# Analogue_Output.net
KiCad netlist of a schematic drawn in Altium Designer
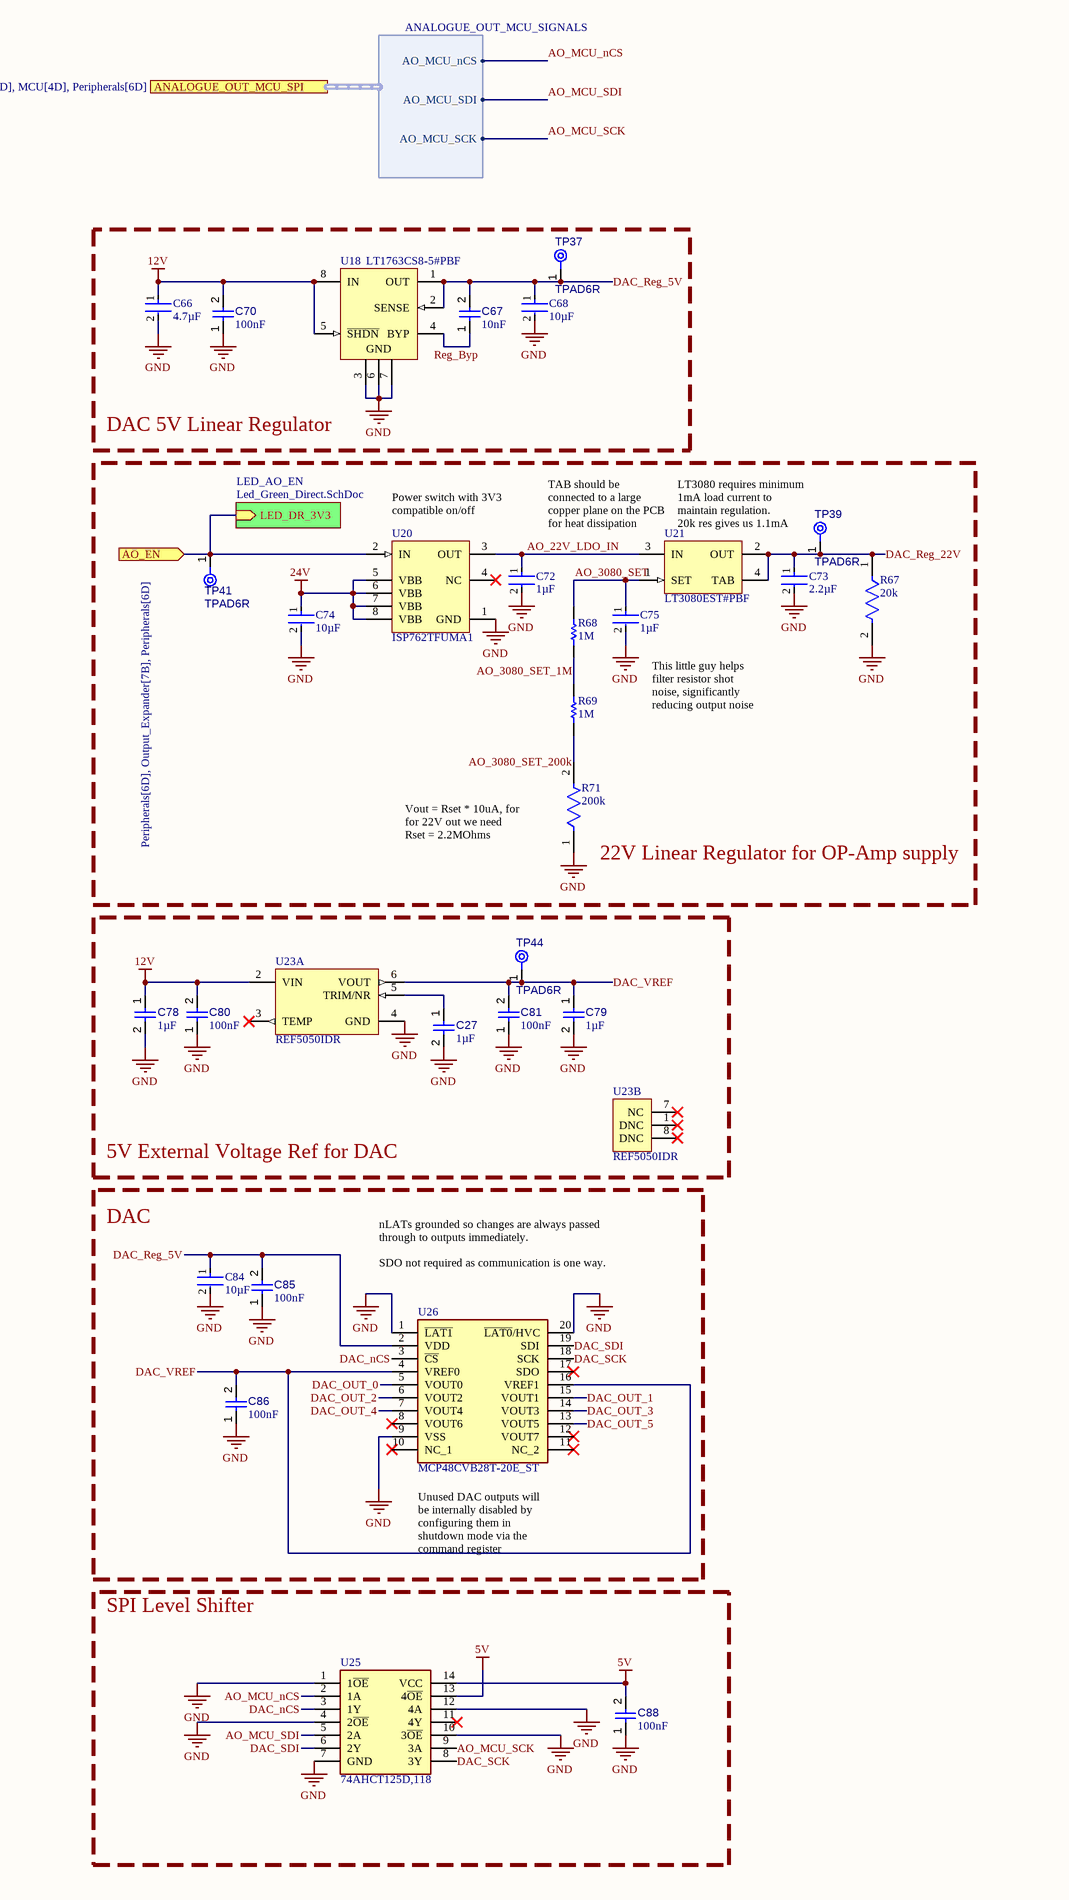
[diagram p0:  Analogue_Output.SchDoc, left]
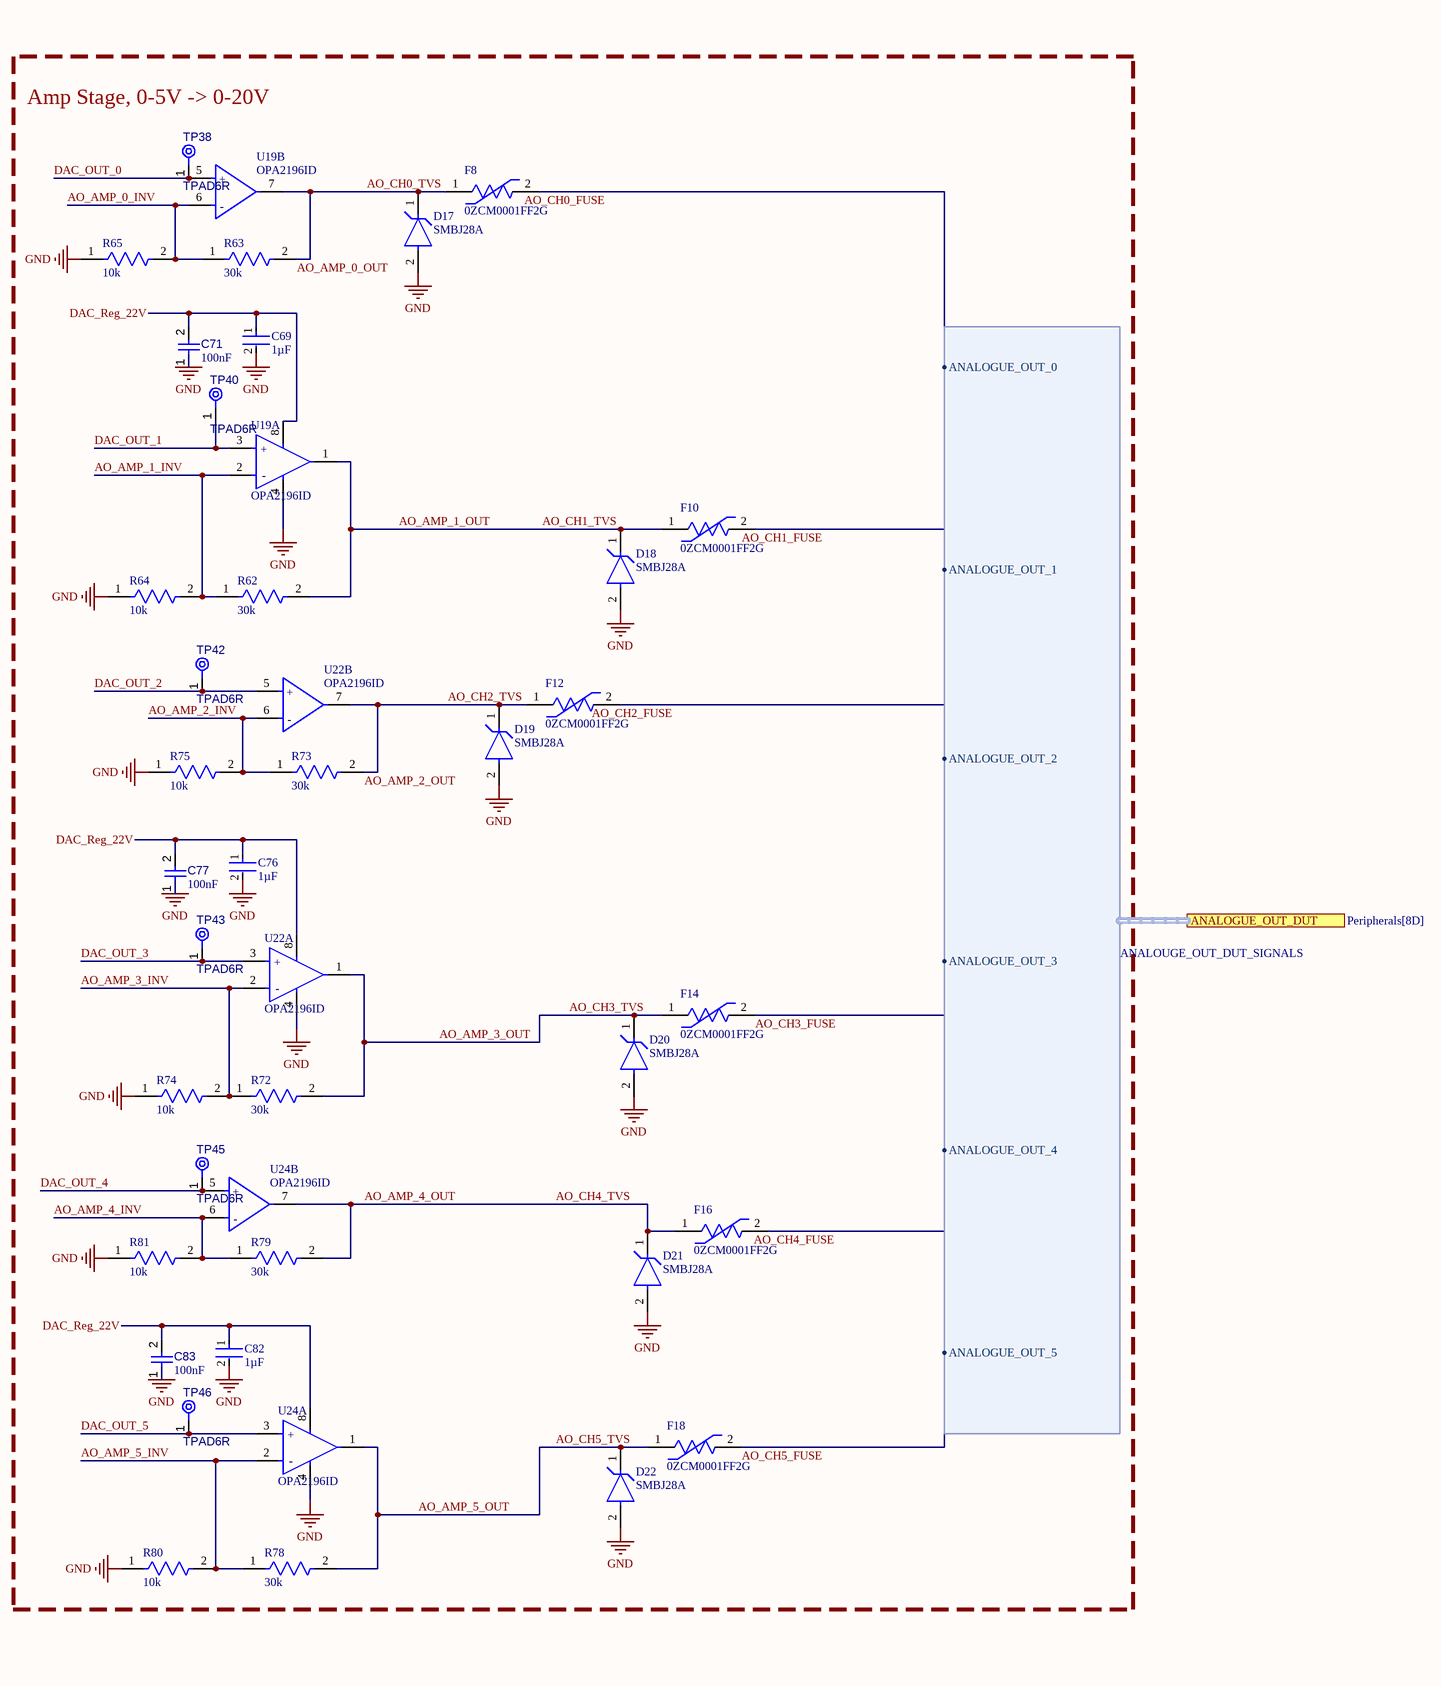
[diagram p1:  Analogue_Output.SchDoc, right]

(export (version "E")
  (design (tool "Eeschema 10.0.6"))
  (components
    (comp (ref "C27")
      (value "1µF")
      (footprint "CAPC1608X90X40LL10T20")
      (description "Chip Capacitor, 1 uF, +/- 10%, 25 V, 0603 (1608 Metric)")
      (fields (field (name "TOLERANCE") "10%") (field (name "Comment") "Capacitor 1 uF +/- 10% 25 V 0603"))
      (libsource (lib "HIL RIG FYP") (part "CAP-NP-2"))
    )
    (comp (ref "C66")
      (value "4.7µF")
      (footprint "FP-GRM21B-0_2-e0_2_0_7-MFG")
      (description "50V 4.7uF X7R ±10% 0805 Multilayer Ceramic Capacitors MLCC - SMD/SMT ROHS")
      (fields (field (name "TOLERANCE") "10%") (field (name "Comment") "GRM21BZ71H475KE15L"))
      (libsource (lib "HIL RIG FYP") (part "b4654b650e69147ec39a6b967a45e02"))
    )
    (comp (ref "C67")
      (value "10nF")
      (footprint "CAPC0402(1005)60_L")
      (description "Chip Capacitor, 10nF +/-20%, 50V, 0402, Thickness 0.6 mm")
      (fields (field (name "TOLERANCE") "5%") (field (name "Comment") "Capacitor 10nF +/-20% 50V 0402"))
      (libsource (lib "HIL RIG FYP") (part "CAP-NP-2"))
    )
    (comp (ref "C68")
      (value "10µF")
      (footprint "FP-GRM31C-0_2-e0_3_0_8-IPC_C")
      (description "25V 10uF X7R ±10% 1206 Multilayer Ceramic Capacitors MLCC - SMD/SMT ROHS")
      (fields (field (name "TOLERANCE") "10%") (field (name "VOLTAGE") "25V"))
      (libsource (lib "HIL RIG FYP") (part "02cd4be3c70576c341d710602a673aa"))
    )
    (comp (ref "C69")
      (value "1µF")
      (footprint "FP-CC0603-DB-IPC_B")
      (description "50V 1uF X7R ±10% 0603 Multilayer Ceramic Capacitors MLCC - SMD/SMT ROHS")
      (fields (field (name "TOLERANCE") "10%") (field (name "Comment") "CC0603KRX7R9BB105"))
      (libsource (lib "HIL RIG FYP") (part "11868f565c42a9108669ba33697ecf6"))
    )
    (comp (ref "C70")
      (value "100nF")
      (footprint "CAPC1608X90X40NL10T20")
      (description "Chip Capacitor, 100 nF, +/- 10%, 50 V, 0603 (1608 Metric)")
      (fields (field (name "TOLERANCE") "10%") (field (name "Comment") "Capacitor 100 nF +/-10% 50 V 0603"))
      (libsource (lib "HIL RIG FYP") (part "CAP-NP-2"))
    )
    (comp (ref "C71")
      (value "100nF")
      (footprint "CAPC1608X90X40NL10T20")
      (description "Chip Capacitor, 100 nF, +/- 10%, 50 V, 0603 (1608 Metric)")
      (fields (field (name "TOLERANCE") "10%") (field (name "Comment") "Capacitor 100 nF +/-10% 50 V 0603"))
      (libsource (lib "HIL RIG FYP") (part "CAP-NP-2"))
    )
    (comp (ref "C72")
      (value "1µF")
      (footprint "FP-CC0603-DB-IPC_B")
      (description "50V 1uF X7R ±10% 0603 Multilayer Ceramic Capacitors MLCC - SMD/SMT ROHS")
      (fields (field (name "TOLERANCE") "10%") (field (name "Comment") "CC0603KRX7R9BB105"))
      (libsource (lib "HIL RIG FYP") (part "11868f565c42a9108669ba33697ecf6"))
    )
    (comp (ref "C73")
      (value "2.2µF")
      (footprint "FP-CC0805-0_85-IPC_A")
      (description "50V 2.2uF X5R ±10% 0805 Multilayer Ceramic Capacitors MLCC - SMD/SMT ROHS")
      (fields (field (name "TOLERANCE") "10%") (field (name "Comment") "CC0805KKX5R9BB225"))
      (libsource (lib "HIL RIG FYP") (part "11868f565c42a9108669ba33697ecf6"))
    )
    (comp (ref "C74")
      (value "10µF")
      (footprint "FP-GRM188-0_2-IPC_C")
      (description "35V 10uF X5R ±20% 0603 Multilayer Ceramic Capacitors MLCC - SMD/SMT ROHS")
      (fields (field (name "TOLERANCE") "20%") (field (name "Comment") "GRM188R6YA106MA73D"))
      (libsource (lib "HIL RIG FYP") (part "11868f565c42a9108669ba33697ecf6"))
    )
    (comp (ref "C75")
      (value "1µF")
      (footprint "FP-CC0603-DB-IPC_B")
      (description "50V 1uF X7R ±10% 0603 Multilayer Ceramic Capacitors MLCC - SMD/SMT ROHS")
      (fields (field (name "TOLERANCE") "10%") (field (name "Comment") "CC0603KRX7R9BB105"))
      (libsource (lib "HIL RIG FYP") (part "11868f565c42a9108669ba33697ecf6"))
    )
    (comp (ref "C76")
      (value "1µF")
      (footprint "FP-CC0603-DB-IPC_B")
      (description "50V 1uF X7R ±10% 0603 Multilayer Ceramic Capacitors MLCC - SMD/SMT ROHS")
      (fields (field (name "TOLERANCE") "10%") (field (name "Comment") "CC0603KRX7R9BB105"))
      (libsource (lib "HIL RIG FYP") (part "11868f565c42a9108669ba33697ecf6"))
    )
    (comp (ref "C77")
      (value "100nF")
      (footprint "CAPC1608X90X40NL10T20")
      (description "Chip Capacitor, 100 nF, +/- 10%, 50 V, 0603 (1608 Metric)")
      (fields (field (name "TOLERANCE") "10%") (field (name "Comment") "Capacitor 100 nF +/-10% 50 V 0603"))
      (libsource (lib "HIL RIG FYP") (part "CAP-NP-2"))
    )
    (comp (ref "C78")
      (value "1µF")
      (footprint "CAPC1608X90X40LL10T20")
      (description "Chip Capacitor, 1 uF, +/- 10%, 25 V, 0603 (1608 Metric)")
      (fields (field (name "TOLERANCE") "10%") (field (name "Comment") "Capacitor 1 uF +/- 10% 25 V 0603"))
      (libsource (lib "HIL RIG FYP") (part "CAP-NP-2"))
    )
    (comp (ref "C79")
      (value "1µF")
      (footprint "CAPC1608X90X40LL10T20")
      (description "Chip Capacitor, 1 uF, +/- 10%, 25 V, 0603 (1608 Metric)")
      (fields (field (name "TOLERANCE") "10%") (field (name "Comment") "Capacitor 1 uF +/- 10% 25 V 0603"))
      (libsource (lib "HIL RIG FYP") (part "CAP-NP-2"))
    )
    (comp (ref "C80")
      (value "100nF")
      (footprint "CAPC1608X90X40NL10T20")
      (description "Chip Capacitor, 100 nF, +/- 10%, 50 V, 0603 (1608 Metric)")
      (fields (field (name "TOLERANCE") "10%") (field (name "Comment") "Capacitor 100 nF +/-10% 50 V 0603"))
      (libsource (lib "HIL RIG FYP") (part "CAP-NP-2"))
    )
    (comp (ref "C81")
      (value "100nF")
      (footprint "CAPC1608X90X40NL10T20")
      (description "Chip Capacitor, 100 nF, +/- 10%, 50 V, 0603 (1608 Metric)")
      (fields (field (name "TOLERANCE") "10%") (field (name "Comment") "Capacitor 100 nF +/-10% 50 V 0603"))
      (libsource (lib "HIL RIG FYP") (part "CAP-NP-2"))
    )
    (comp (ref "C82")
      (value "1µF")
      (footprint "FP-CC0603-DB-IPC_B")
      (description "50V 1uF X7R ±10% 0603 Multilayer Ceramic Capacitors MLCC - SMD/SMT ROHS")
      (fields (field (name "TOLERANCE") "10%") (field (name "Comment") "CC0603KRX7R9BB105"))
      (libsource (lib "HIL RIG FYP") (part "11868f565c42a9108669ba33697ecf6"))
    )
    (comp (ref "C83")
      (value "100nF")
      (footprint "CAPC1608X90X40NL10T20")
      (description "Chip Capacitor, 100 nF, +/- 10%, 50 V, 0603 (1608 Metric)")
      (fields (field (name "TOLERANCE") "10%") (field (name "Comment") "Capacitor 100 nF +/-10% 50 V 0603"))
      (libsource (lib "HIL RIG FYP") (part "CAP-NP-2"))
    )
    (comp (ref "C84")
      (value "10µF")
      (footprint "FP-GRM31C-0_2-e0_3_0_8-IPC_C")
      (description "25V 10uF X7R ±10% 1206 Multilayer Ceramic Capacitors MLCC - SMD/SMT ROHS")
      (fields (field (name "TOLERANCE") "10%") (field (name "VOLTAGE") "25V"))
      (libsource (lib "HIL RIG FYP") (part "02cd4be3c70576c341d710602a673aa"))
    )
    (comp (ref "C85")
      (value "100nF")
      (footprint "CAPC1608X90X40NL10T20")
      (description "Chip Capacitor, 100 nF, +/- 10%, 50 V, 0603 (1608 Metric)")
      (fields (field (name "TOLERANCE") "10%") (field (name "Comment") "Capacitor 100 nF +/-10% 50 V 0603"))
      (libsource (lib "HIL RIG FYP") (part "CAP-NP-2"))
    )
    (comp (ref "C86")
      (value "100nF")
      (footprint "CAPC1608X90X40NL10T20")
      (description "Chip Capacitor, 100 nF, +/- 10%, 50 V, 0603 (1608 Metric)")
      (fields (field (name "TOLERANCE") "10%") (field (name "Comment") "Capacitor 100 nF +/-10% 50 V 0603"))
      (libsource (lib "HIL RIG FYP") (part "CAP-NP-2"))
    )
    (comp (ref "C88")
      (value "100nF")
      (footprint "CAPC1608X90X40NL10T20")
      (description "Chip Capacitor, 100 nF, +/- 10%, 50 V, 0603 (1608 Metric)")
      (fields (field (name "TOLERANCE") "10%") (field (name "Comment") "Capacitor 100 nF +/-10% 50 V 0603"))
      (libsource (lib "HIL RIG FYP") (part "CAP-NP-2"))
    )
    (comp (ref "D17")
      (value "SMBJ28A")
      (footprint "FP-SMBJ-MFG")
      (description "Tvs Diodes & Esd Suppressors; SMBJ28A; Littelfuse; 28 V; 45.4 V; 31.1 V; 31.1 V")
      (fields (field (name "VOLTAGE") "28V"))
      (libsource (lib "HIL RIG FYP") (part "f813f71cba58e380607f5dd3caf9714"))
    )
    (comp (ref "D18")
      (value "SMBJ28A")
      (footprint "FP-SMBJ-MFG")
      (description "Tvs Diodes & Esd Suppressors; SMBJ28A; Littelfuse; 28 V; 45.4 V; 31.1 V; 31.1 V")
      (fields (field (name "VOLTAGE") "28V"))
      (libsource (lib "HIL RIG FYP") (part "f813f71cba58e380607f5dd3caf9714"))
    )
    (comp (ref "D19")
      (value "SMBJ28A")
      (footprint "FP-SMBJ-MFG")
      (description "Tvs Diodes & Esd Suppressors; SMBJ28A; Littelfuse; 28 V; 45.4 V; 31.1 V; 31.1 V")
      (fields (field (name "VOLTAGE") "28V"))
      (libsource (lib "HIL RIG FYP") (part "f813f71cba58e380607f5dd3caf9714"))
    )
    (comp (ref "D20")
      (value "SMBJ28A")
      (footprint "FP-SMBJ-MFG")
      (description "Tvs Diodes & Esd Suppressors; SMBJ28A; Littelfuse; 28 V; 45.4 V; 31.1 V; 31.1 V")
      (fields (field (name "VOLTAGE") "28V"))
      (libsource (lib "HIL RIG FYP") (part "f813f71cba58e380607f5dd3caf9714"))
    )
    (comp (ref "D21")
      (value "SMBJ28A")
      (footprint "FP-SMBJ-MFG")
      (description "Tvs Diodes & Esd Suppressors; SMBJ28A; Littelfuse; 28 V; 45.4 V; 31.1 V; 31.1 V")
      (fields (field (name "VOLTAGE") "28V"))
      (libsource (lib "HIL RIG FYP") (part "f813f71cba58e380607f5dd3caf9714"))
    )
    (comp (ref "D22")
      (value "SMBJ28A")
      (footprint "FP-SMBJ-MFG")
      (description "Tvs Diodes & Esd Suppressors; SMBJ28A; Littelfuse; 28 V; 45.4 V; 31.1 V; 31.1 V")
      (fields (field (name "VOLTAGE") "28V"))
      (libsource (lib "HIL RIG FYP") (part "f813f71cba58e380607f5dd3caf9714"))
    )
    (comp (ref "F8")
      (value "0ZCM0001FF2G")
      (footprint "FP-0ZCM0001FF2G-MFG")
      (description "Prices include import duty and tax. RESETTABLE PTC FUSE, SMD, 0603 SIZE, 10MA, 60V;")
      (libsource (lib "HIL RIG FYP") (part "1c6d77a0208143737455a0c7eb396be"))
    )
    (comp (ref "F10")
      (value "0ZCM0001FF2G")
      (footprint "FP-0ZCM0001FF2G-MFG")
      (description "Prices include import duty and tax. RESETTABLE PTC FUSE, SMD, 0603 SIZE, 10MA, 60V;")
      (libsource (lib "HIL RIG FYP") (part "1c6d77a0208143737455a0c7eb396be"))
    )
    (comp (ref "F12")
      (value "0ZCM0001FF2G")
      (footprint "FP-0ZCM0001FF2G-MFG")
      (description "Prices include import duty and tax. RESETTABLE PTC FUSE, SMD, 0603 SIZE, 10MA, 60V;")
      (libsource (lib "HIL RIG FYP") (part "1c6d77a0208143737455a0c7eb396be"))
    )
    (comp (ref "F14")
      (value "0ZCM0001FF2G")
      (footprint "FP-0ZCM0001FF2G-MFG")
      (description "Prices include import duty and tax. RESETTABLE PTC FUSE, SMD, 0603 SIZE, 10MA, 60V;")
      (libsource (lib "HIL RIG FYP") (part "1c6d77a0208143737455a0c7eb396be"))
    )
    (comp (ref "F16")
      (value "0ZCM0001FF2G")
      (footprint "FP-0ZCM0001FF2G-MFG")
      (description "Prices include import duty and tax. RESETTABLE PTC FUSE, SMD, 0603 SIZE, 10MA, 60V;")
      (libsource (lib "HIL RIG FYP") (part "1c6d77a0208143737455a0c7eb396be"))
    )
    (comp (ref "F18")
      (value "0ZCM0001FF2G")
      (footprint "FP-0ZCM0001FF2G-MFG")
      (description "Prices include import duty and tax. RESETTABLE PTC FUSE, SMD, 0603 SIZE, 10MA, 60V;")
      (libsource (lib "HIL RIG FYP") (part "1c6d77a0208143737455a0c7eb396be"))
    )
    (comp (ref "R62")
      (value "30k")
      (footprint "FP-RT0603-IPC_C")
      (description "100mW Thin Film Resistor ±50ppm/℃ ±0.1% 30kΩ 0603 Chip Resistor - Surface Mount ROHS")
      (fields (field (name "TOLERANCE") "0.1%") (field (name "Comment") "RT0603BRE0730KL"))
      (libsource (lib "HIL RIG FYP") (part "1029c3af85768c4190bb7ad29bc67b5"))
    )
    (comp (ref "R63")
      (value "30k")
      (footprint "FP-RT0603-IPC_C")
      (description "100mW Thin Film Resistor ±50ppm/℃ ±0.1% 30kΩ 0603 Chip Resistor - Surface Mount ROHS")
      (fields (field (name "TOLERANCE") "0.1%") (field (name "Comment") "RT0603BRE0730KL"))
      (libsource (lib "HIL RIG FYP") (part "1029c3af85768c4190bb7ad29bc67b5"))
    )
    (comp (ref "R64")
      (value "10k")
      (footprint "FP-RT0603-IPC_C")
      (description "Res Thin Film 0603 10K Ohm 0.1% 1/10W ¦25ppm/¦C SMD Paper T/R")
      (fields (field (name "TOLERANCE") "0.1%") (field (name "Comment") "RT0603BRD0710KL"))
      (libsource (lib "HIL RIG FYP") (part "1029c3af85768c4190bb7ad29bc67b5"))
    )
    (comp (ref "R65")
      (value "10k")
      (footprint "FP-RT0603-IPC_C")
      (description "Res Thin Film 0603 10K Ohm 0.1% 1/10W ¦25ppm/¦C SMD Paper T/R")
      (fields (field (name "TOLERANCE") "0.1%") (field (name "Comment") "RT0603BRD0710KL"))
      (libsource (lib "HIL RIG FYP") (part "1029c3af85768c4190bb7ad29bc67b5"))
    )
    (comp (ref "R67")
      (value "20k")
      (footprint "FP-RT0603-IPC_C")
      (description "100mW Thin Film Resistor 75V ±0.5% ±25ppm/℃ 20kΩ 0603 Chip Resistor - Surface Mount ROHS")
      (fields (field (name "TOLERANCE") "0.5%") (field (name "Comment") "RT0603DRD0720KL"))
      (libsource (lib "HIL RIG FYP") (part "1029c3af85768c4190bb7ad29bc67b5"))
    )
    (comp (ref "R68")
      (value "1M")
      (footprint "RESC2013X60X35ML10T20")
      (fields (field (name "TOLERANCE") "0.1%") (field (name "Comment") "RT0805BRD071ML"))
      (libsource (lib "HIL RIG FYP") (part "RES"))
    )
    (comp (ref "R69")
      (value "1M")
      (footprint "RESC2013X60X35ML10T20")
      (fields (field (name "TOLERANCE") "0.1%") (field (name "Comment") "RT0805BRD071ML"))
      (libsource (lib "HIL RIG FYP") (part "RES"))
    )
    (comp (ref "R71")
      (value "200k")
      (footprint "FP-AT0603-IPC_A")
      (description "100mW Thin Film Resistor ±25ppm/℃ ±0.1% 200kΩ 0603 Chip Resistor - Surface Mount ROHS")
      (fields (field (name "TOLERANCE") "0.1%") (field (name "Comment") "AT0603BRD07200KL"))
      (libsource (lib "HIL RIG FYP") (part "1029c3af85768c4190bb7ad29bc67b5"))
    )
    (comp (ref "R72")
      (value "30k")
      (footprint "FP-RT0603-IPC_C")
      (description "100mW Thin Film Resistor ±50ppm/℃ ±0.1% 30kΩ 0603 Chip Resistor - Surface Mount ROHS")
      (fields (field (name "TOLERANCE") "0.1%") (field (name "Comment") "RT0603BRE0730KL"))
      (libsource (lib "HIL RIG FYP") (part "1029c3af85768c4190bb7ad29bc67b5"))
    )
    (comp (ref "R73")
      (value "30k")
      (footprint "FP-RT0603-IPC_C")
      (description "100mW Thin Film Resistor ±50ppm/℃ ±0.1% 30kΩ 0603 Chip Resistor - Surface Mount ROHS")
      (fields (field (name "TOLERANCE") "0.1%") (field (name "Comment") "RT0603BRE0730KL"))
      (libsource (lib "HIL RIG FYP") (part "1029c3af85768c4190bb7ad29bc67b5"))
    )
    (comp (ref "R74")
      (value "10k")
      (footprint "FP-RT0603-IPC_C")
      (description "Res Thin Film 0603 10K Ohm 0.1% 1/10W ¦25ppm/¦C SMD Paper T/R")
      (fields (field (name "TOLERANCE") "0.1%") (field (name "Comment") "RT0603BRD0710KL"))
      (libsource (lib "HIL RIG FYP") (part "1029c3af85768c4190bb7ad29bc67b5"))
    )
    (comp (ref "R75")
      (value "10k")
      (footprint "FP-RT0603-IPC_C")
      (description "Res Thin Film 0603 10K Ohm 0.1% 1/10W ¦25ppm/¦C SMD Paper T/R")
      (fields (field (name "TOLERANCE") "0.1%") (field (name "Comment") "RT0603BRD0710KL"))
      (libsource (lib "HIL RIG FYP") (part "1029c3af85768c4190bb7ad29bc67b5"))
    )
    (comp (ref "R78")
      (value "30k")
      (footprint "FP-RT0603-IPC_C")
      (description "100mW Thin Film Resistor ±50ppm/℃ ±0.1% 30kΩ 0603 Chip Resistor - Surface Mount ROHS")
      (fields (field (name "TOLERANCE") "0.1%") (field (name "Comment") "RT0603BRE0730KL"))
      (libsource (lib "HIL RIG FYP") (part "1029c3af85768c4190bb7ad29bc67b5"))
    )
    (comp (ref "R79")
      (value "30k")
      (footprint "FP-RT0603-IPC_C")
      (description "100mW Thin Film Resistor ±50ppm/℃ ±0.1% 30kΩ 0603 Chip Resistor - Surface Mount ROHS")
      (fields (field (name "TOLERANCE") "0.1%") (field (name "Comment") "RT0603BRE0730KL"))
      (libsource (lib "HIL RIG FYP") (part "1029c3af85768c4190bb7ad29bc67b5"))
    )
    (comp (ref "R80")
      (value "10k")
      (footprint "FP-RT0603-IPC_C")
      (description "Res Thin Film 0603 10K Ohm 0.1% 1/10W ¦25ppm/¦C SMD Paper T/R")
      (fields (field (name "TOLERANCE") "0.1%") (field (name "Comment") "RT0603BRD0710KL"))
      (libsource (lib "HIL RIG FYP") (part "1029c3af85768c4190bb7ad29bc67b5"))
    )
    (comp (ref "R81")
      (value "10k")
      (footprint "FP-RT0603-IPC_C")
      (description "Res Thin Film 0603 10K Ohm 0.1% 1/10W ¦25ppm/¦C SMD Paper T/R")
      (fields (field (name "TOLERANCE") "0.1%") (field (name "Comment") "RT0603BRD0710KL"))
      (libsource (lib "HIL RIG FYP") (part "1029c3af85768c4190bb7ad29bc67b5"))
    )
    (comp (ref "TP37")
      (value "TPAD6R")
      (footprint "TP06R")
      (description "0.6mm round")
      (libsource (lib "HIL RIG FYP") (part "CMP-001-0001-4"))
    )
    (comp (ref "TP38")
      (value "TPAD6R")
      (footprint "TP06R")
      (description "0.6mm round")
      (libsource (lib "HIL RIG FYP") (part "CMP-001-0001-4"))
    )
    (comp (ref "TP39")
      (value "TPAD6R")
      (footprint "TP06R")
      (description "0.6mm round")
      (libsource (lib "HIL RIG FYP") (part "CMP-001-0001-4"))
    )
    (comp (ref "TP40")
      (value "TPAD6R")
      (footprint "TP06R")
      (description "0.6mm round")
      (libsource (lib "HIL RIG FYP") (part "CMP-001-0001-4"))
    )
    (comp (ref "TP41")
      (value "TPAD6R")
      (footprint "TP06R")
      (description "0.6mm round")
      (libsource (lib "HIL RIG FYP") (part "CMP-001-0001-4"))
    )
    (comp (ref "TP42")
      (value "TPAD6R")
      (footprint "TP06R")
      (description "0.6mm round")
      (libsource (lib "HIL RIG FYP") (part "CMP-001-0001-4"))
    )
    (comp (ref "TP43")
      (value "TPAD6R")
      (footprint "TP06R")
      (description "0.6mm round")
      (libsource (lib "HIL RIG FYP") (part "CMP-001-0001-4"))
    )
    (comp (ref "TP44")
      (value "TPAD6R")
      (footprint "TP06R")
      (description "0.6mm round")
      (libsource (lib "HIL RIG FYP") (part "CMP-001-0001-4"))
    )
    (comp (ref "TP45")
      (value "TPAD6R")
      (footprint "TP06R")
      (description "0.6mm round")
      (libsource (lib "HIL RIG FYP") (part "CMP-001-0001-4"))
    )
    (comp (ref "TP46")
      (value "TPAD6R")
      (footprint "TP06R")
      (description "0.6mm round")
      (libsource (lib "HIL RIG FYP") (part "CMP-001-0001-4"))
    )
    (comp (ref "U18")
      (value "LT1763CS8-5#PBF")
      (footprint "LT-S8-8_N")
      (description "LDO Regulator Pos 5V 0.5A Automotive 8-Pin SOIC N Tube / IC REG LDO 5V 0.5A 8SOIC")
      (libsource (lib "HIL RIG FYP") (part "LT-LT1763-S8-8"))
    )
    (comp (ref "U19")
      (value "OPA2196ID")
      (footprint "FP-D0008A-IPC_B")
      (description "IC OPAMP GP 2 CIRCUIT 8SOIC / General Purpose Amplifier 2 Circuit Rail-to-Rail 8-SOIC")
      (libsource (lib "HIL RIG FYP") (part "499df5fc91ff7ad023bcaf249d8becd"))
    )
    (comp (ref "U20")
      (value "ISP762TFUMA1")
      (footprint "INF-PG-DSO-8-3_L")
      (description "ISP452 Series 34 V 100 mOhm SMT Smart Power High Side Switch - PG-DSO-8")
      (fields (field (name "VOLTAGE") "16V"))
      (libsource (lib "HIL RIG FYP") (part "INF-ISP762T-PG-DSO-8-3-8"))
    )
    (comp (ref "U21")
      (value "LT3080EST#PBF")
      (footprint "LT-ST-3-SOT-223_M")
      (description "LDO Regulator Pos 0V to 30V 1.1A Automotive 4-Pin(3+Tab) SOT-223")
      (libsource (lib "HIL RIG FYP") (part "LT-LT30XX-ST-3"))
    )
    (comp (ref "U22")
      (value "OPA2196ID")
      (footprint "FP-D0008A-IPC_B")
      (description "IC OPAMP GP 2 CIRCUIT 8SOIC / General Purpose Amplifier 2 Circuit Rail-to-Rail 8-SOIC")
      (libsource (lib "HIL RIG FYP") (part "499df5fc91ff7ad023bcaf249d8becd"))
    )
    (comp (ref "U23")
      (value "REF5050IDR")
      (footprint "D0008A_L")
      (description "Low-noise, very low-drift, wide-VIN precision voltage reference 8-SOIC -40 to 125")
      (fields (field (name "TOLERANCE") "0.05%"))
      (libsource (lib "HIL RIG FYP") (part "TI-REF5050D8"))
    )
    (comp (ref "U24")
      (value "OPA2196ID")
      (footprint "FP-D0008A-IPC_B")
      (description "IC OPAMP GP 2 CIRCUIT 8SOIC / General Purpose Amplifier 2 Circuit Rail-to-Rail 8-SOIC")
      (libsource (lib "HIL RIG FYP") (part "499df5fc91ff7ad023bcaf249d8becd"))
    )
    (comp (ref "U25")
      (value "74AHCT125D,118")
      (footprint "SamacSys:SOIC127P600X175-14N")
      (description "Integrated Circuit")
      (fields (field (name "MOUSER PART NUMBER") "771-AHCT125D118"))
      (libsource (lib "*") (part "74AHCT125D,118"))
    )
    (comp (ref "U26")
      (value "MCP48CVB28T-20E_ST")
      (footprint "SOP65P640X120-20N")
      (description "Digital to Analog Converters - DAC Qctal Channel")
      (fields
        (field (name "MOUSER PART NUMBER") "579-MCP48CVB28T20EST")
        (field (name "MANUFACTURER_PART_NUMBER") "MCP48CVB28T-20E/ST")
      )
      (libsource (lib "HIL RIG FYP") (part "MCP48CVB28T-20E_ST"))
    )
  )
  (nets
    (net (code "3") (name "/AO_22V_LDO_IN") (class "Default")
      (node (ref "C72") (pin "1") (pinfunction "1_1") (pintype "passive"))
      (node (ref "U20") (pin "3") (pinfunction "OUT_3") (pintype "power_in"))
      (node (ref "U21") (pin "3") (pinfunction "IN_3") (pintype "power_in"))
    )
    (net (code "4") (name "/AO_3080_SET") (class "Default")
      (node (ref "C75") (pin "1") (pinfunction "1_1") (pintype "passive"))
      (node (ref "R68") (pin "1") (pinfunction "1_1") (pintype "passive"))
      (node (ref "U21") (pin "1") (pinfunction "SET_1") (pintype "input"))
    )
    (net (code "5") (name "/AO_3080_SET_1M") (class "Default")
      (node (ref "R68") (pin "2") (pinfunction "2_2") (pintype "passive"))
      (node (ref "R69") (pin "1") (pinfunction "1_1") (pintype "passive"))
    )
    (net (code "6") (name "/AO_3080_SET_200k") (class "Default")
      (node (ref "R69") (pin "2") (pinfunction "2_2") (pintype "passive"))
      (node (ref "R71") (pin "2") (pinfunction "2_2") (pintype "passive"))
    )
    (net (code "7") (name "/AO_AMP_0_INV") (class "Default")
      (node (ref "R63") (pin "1") (pinfunction "1_1") (pintype "passive"))
      (node (ref "R65") (pin "2") (pinfunction "2_2") (pintype "passive"))
      (node (ref "U19") (pin "6") (pinfunction "-IN_B_6") (pintype "tri_state"))
    )
    (net (code "8") (name "/AO_AMP_0_OUT") (class "Default")
      (node (ref "D17") (pin "1") (pinfunction "C_1") (pintype "passive"))
      (node (ref "F8") (pin "1") (pinfunction "1_1") (pintype "passive"))
      (node (ref "R63") (pin "2") (pinfunction "2_2") (pintype "passive"))
      (node (ref "U19") (pin "7") (pinfunction "OUT_B_7") (pintype "passive"))
    )
    (net (code "9") (name "/AO_AMP_1_INV") (class "Default")
      (node (ref "R62") (pin "1") (pinfunction "1_1") (pintype "passive"))
      (node (ref "R64") (pin "2") (pinfunction "2_2") (pintype "passive"))
      (node (ref "U19") (pin "2") (pinfunction "-IN_A_2") (pintype "tri_state"))
    )
    (net (code "10") (name "/AO_AMP_1_OUT") (class "Default")
      (node (ref "D18") (pin "1") (pinfunction "C_1") (pintype "passive"))
      (node (ref "F10") (pin "1") (pinfunction "1_1") (pintype "passive"))
      (node (ref "R62") (pin "2") (pinfunction "2_2") (pintype "passive"))
      (node (ref "U19") (pin "1") (pinfunction "OUT_A_1") (pintype "passive"))
    )
    (net (code "11") (name "/AO_AMP_2_INV") (class "Default")
      (node (ref "R73") (pin "1") (pinfunction "1_1") (pintype "passive"))
      (node (ref "R75") (pin "2") (pinfunction "2_2") (pintype "passive"))
      (node (ref "U22") (pin "6") (pinfunction "-IN_B_6") (pintype "tri_state"))
    )
    (net (code "12") (name "/AO_AMP_2_OUT") (class "Default")
      (node (ref "D19") (pin "1") (pinfunction "C_1") (pintype "passive"))
      (node (ref "F12") (pin "1") (pinfunction "1_1") (pintype "passive"))
      (node (ref "R73") (pin "2") (pinfunction "2_2") (pintype "passive"))
      (node (ref "U22") (pin "7") (pinfunction "OUT_B_7") (pintype "passive"))
    )
    (net (code "13") (name "/AO_AMP_3_INV") (class "Default")
      (node (ref "R72") (pin "1") (pinfunction "1_1") (pintype "passive"))
      (node (ref "R74") (pin "2") (pinfunction "2_2") (pintype "passive"))
      (node (ref "U22") (pin "2") (pinfunction "-IN_A_2") (pintype "tri_state"))
    )
    (net (code "14") (name "/AO_AMP_3_OUT") (class "Default")
      (node (ref "D20") (pin "1") (pinfunction "C_1") (pintype "passive"))
      (node (ref "F14") (pin "1") (pinfunction "1_1") (pintype "passive"))
      (node (ref "R72") (pin "2") (pinfunction "2_2") (pintype "passive"))
      (node (ref "U22") (pin "1") (pinfunction "OUT_A_1") (pintype "passive"))
    )
    (net (code "15") (name "/AO_AMP_4_INV") (class "Default")
      (node (ref "R79") (pin "1") (pinfunction "1_1") (pintype "passive"))
      (node (ref "R81") (pin "2") (pinfunction "2_2") (pintype "passive"))
      (node (ref "U24") (pin "6") (pinfunction "-IN_B_6") (pintype "tri_state"))
    )
    (net (code "16") (name "/AO_AMP_4_OUT") (class "Default")
      (node (ref "D21") (pin "1") (pinfunction "C_1") (pintype "passive"))
      (node (ref "F16") (pin "1") (pinfunction "1_1") (pintype "passive"))
      (node (ref "R79") (pin "2") (pinfunction "2_2") (pintype "passive"))
      (node (ref "U24") (pin "7") (pinfunction "OUT_B_7") (pintype "passive"))
    )
    (net (code "17") (name "/AO_AMP_5_INV") (class "Default")
      (node (ref "R78") (pin "1") (pinfunction "1_1") (pintype "passive"))
      (node (ref "R80") (pin "2") (pinfunction "2_2") (pintype "passive"))
      (node (ref "U24") (pin "2") (pinfunction "-IN_A_2") (pintype "tri_state"))
    )
    (net (code "18") (name "/AO_AMP_5_OUT") (class "Default")
      (node (ref "D22") (pin "1") (pinfunction "C_1") (pintype "passive"))
      (node (ref "F18") (pin "1") (pinfunction "1_1") (pintype "passive"))
      (node (ref "R78") (pin "2") (pinfunction "2_2") (pintype "passive"))
      (node (ref "U24") (pin "1") (pinfunction "OUT_A_1") (pintype "passive"))
    )
    (net (code "19") (name "/AO_CH0_FUSE") (class "Default")
      (node (ref "F8") (pin "2") (pinfunction "2_2") (pintype "passive"))
    )
    (net (code "20") (name "/AO_CH1_FUSE") (class "Default")
      (node (ref "F10") (pin "2") (pinfunction "2_2") (pintype "passive"))
    )
    (net (code "21") (name "/AO_CH2_FUSE") (class "Default")
      (node (ref "F12") (pin "2") (pinfunction "2_2") (pintype "passive"))
    )
    (net (code "22") (name "/AO_CH3_FUSE") (class "Default")
      (node (ref "F14") (pin "2") (pinfunction "2_2") (pintype "passive"))
    )
    (net (code "23") (name "/AO_CH4_FUSE") (class "Default")
      (node (ref "F16") (pin "2") (pinfunction "2_2") (pintype "passive"))
    )
    (net (code "24") (name "/AO_CH5_FUSE") (class "Default")
      (node (ref "F18") (pin "2") (pinfunction "2_2") (pintype "passive"))
    )
    (net (code "25") (name "/AO_EN") (class "Default")
      (node (ref "TP41") (pin "1") (pinfunction "TP_1") (pintype "passive"))
      (node (ref "U20") (pin "2") (pinfunction "IN_2") (pintype "input"))
    )
    (net (code "26") (name "/AO_MCU_SCK") (class "Default")
      (node (ref "U25") (pin "9") (pinfunction "3A_9") (pintype "passive"))
    )
    (net (code "27") (name "/AO_MCU_SDI") (class "Default")
      (node (ref "U25") (pin "5") (pinfunction "2A_5") (pintype "passive"))
    )
    (net (code "28") (name "/AO_MCU_nCS") (class "Default")
      (node (ref "U25") (pin "2") (pinfunction "1A_2") (pintype "passive"))
    )
    (net (code "29") (name "/DAC_OUT_0") (class "Default")
      (node (ref "TP38") (pin "1") (pinfunction "TP_1") (pintype "passive"))
      (node (ref "U19") (pin "5") (pinfunction "+IN_B_5") (pintype "tri_state"))
      (node (ref "U26") (pin "5") (pinfunction "VOUT0_5") (pintype "passive"))
    )
    (net (code "30") (name "/DAC_OUT_1") (class "Default")
      (node (ref "TP40") (pin "1") (pinfunction "TP_1") (pintype "passive"))
      (node (ref "U19") (pin "3") (pinfunction "+IN_A_3") (pintype "tri_state"))
      (node (ref "U26") (pin "15") (pinfunction "VOUT1_15") (pintype "passive"))
    )
    (net (code "31") (name "/DAC_OUT_2") (class "Default")
      (node (ref "TP42") (pin "1") (pinfunction "TP_1") (pintype "passive"))
      (node (ref "U22") (pin "5") (pinfunction "+IN_B_5") (pintype "tri_state"))
      (node (ref "U26") (pin "6") (pinfunction "VOUT2_6") (pintype "passive"))
    )
    (net (code "32") (name "/DAC_OUT_3") (class "Default")
      (node (ref "TP43") (pin "1") (pinfunction "TP_1") (pintype "passive"))
      (node (ref "U22") (pin "3") (pinfunction "+IN_A_3") (pintype "tri_state"))
      (node (ref "U26") (pin "14") (pinfunction "VOUT3_14") (pintype "passive"))
    )
    (net (code "33") (name "/DAC_OUT_4") (class "Default")
      (node (ref "TP45") (pin "1") (pinfunction "TP_1") (pintype "passive"))
      (node (ref "U24") (pin "5") (pinfunction "+IN_B_5") (pintype "tri_state"))
      (node (ref "U26") (pin "7") (pinfunction "VOUT4_7") (pintype "passive"))
    )
    (net (code "34") (name "/DAC_OUT_5") (class "Default")
      (node (ref "TP46") (pin "1") (pinfunction "TP_1") (pintype "passive"))
      (node (ref "U24") (pin "3") (pinfunction "+IN_A_3") (pintype "tri_state"))
      (node (ref "U26") (pin "13") (pinfunction "VOUT5_13") (pintype "passive"))
    )
    (net (code "35") (name "/DAC_Reg_5V") (class "Default")
      (node (ref "C67") (pin "2") (pinfunction "2_2") (pintype "passive"))
      (node (ref "C68") (pin "1") (pinfunction "1_1") (pintype "passive"))
      (node (ref "C84") (pin "1") (pinfunction "1_1") (pintype "passive"))
      (node (ref "C85") (pin "2") (pinfunction "2_2") (pintype "passive"))
      (node (ref "TP37") (pin "1") (pinfunction "TP_1") (pintype "passive"))
      (node (ref "U18") (pin "1") (pinfunction "OUT_1") (pintype "power_in"))
      (node (ref "U18") (pin "2") (pinfunction "SENSE_2") (pintype "input"))
      (node (ref "U26") (pin "2") (pinfunction "VDD_2") (pintype "passive"))
    )
    (net (code "36") (name "/DAC_Reg_22V") (class "Default")
      (node (ref "C69") (pin "1") (pinfunction "1_1") (pintype "passive"))
      (node (ref "C71") (pin "2") (pinfunction "2_2") (pintype "passive"))
      (node (ref "C73") (pin "1") (pinfunction "1_1") (pintype "passive"))
      (node (ref "C76") (pin "1") (pinfunction "1_1") (pintype "passive"))
      (node (ref "C77") (pin "2") (pinfunction "2_2") (pintype "passive"))
      (node (ref "C82") (pin "1") (pinfunction "1_1") (pintype "passive"))
      (node (ref "C83") (pin "2") (pinfunction "2_2") (pintype "passive"))
      (node (ref "R67") (pin "1") (pinfunction "1_1") (pintype "passive"))
      (node (ref "TP39") (pin "1") (pinfunction "TP_1") (pintype "passive"))
      (node (ref "U19") (pin "8") (pinfunction "V+_8") (pintype "power_in"))
      (node (ref "U21") (pin "2") (pinfunction "OUT_2") (pintype "power_in"))
      (node (ref "U21") (pin "4") (pinfunction "TAB_4") (pintype "power_in"))
      (node (ref "U22") (pin "8") (pinfunction "V+_8") (pintype "power_in"))
      (node (ref "U24") (pin "8") (pinfunction "V+_8") (pintype "power_in"))
    )
    (net (code "37") (name "/DAC_SCK") (class "Default")
      (node (ref "U25") (pin "8") (pinfunction "3Y_8") (pintype "passive"))
      (node (ref "U26") (pin "18") (pinfunction "SCK_18") (pintype "passive"))
    )
    (net (code "38") (name "/DAC_SDI") (class "Default")
      (node (ref "U25") (pin "6") (pinfunction "2Y_6") (pintype "passive"))
      (node (ref "U26") (pin "19") (pinfunction "SDI_19") (pintype "passive"))
    )
    (net (code "39") (name "/DAC_VREF") (class "Default")
      (node (ref "C79") (pin "1") (pinfunction "1_1") (pintype "passive"))
      (node (ref "C81") (pin "2") (pinfunction "2_2") (pintype "passive"))
      (node (ref "C86") (pin "2") (pinfunction "2_2") (pintype "passive"))
      (node (ref "TP44") (pin "1") (pinfunction "TP_1") (pintype "passive"))
      (node (ref "U23") (pin "6") (pinfunction "VOUT_6") (pintype "output"))
      (node (ref "U26") (pin "16") (pinfunction "VREF1_16") (pintype "passive"))
      (node (ref "U26") (pin "4") (pinfunction "VREF0_4") (pintype "passive"))
    )
    (net (code "40") (name "/DAC_nCS") (class "Default")
      (node (ref "U25") (pin "3") (pinfunction "1Y_3") (pintype "passive"))
      (node (ref "U26") (pin "3") (pinfunction "~{CS}_3") (pintype "passive"))
    )
    (net (code "41") (name "/Reg_Byp") (class "Default")
      (node (ref "C67") (pin "1") (pinfunction "1_1") (pintype "passive"))
      (node (ref "U18") (pin "4") (pinfunction "BYP_4") (pintype "passive"))
    )
    (net (code "44") (name "5V") (class "Default")
      (node (ref "C88") (pin "2") (pinfunction "2_2") (pintype "passive"))
      (node (ref "U25") (pin "13") (pinfunction "4~{OE}_13") (pintype "passive"))
      (node (ref "U25") (pin "14") (pinfunction "VCC_14") (pintype "passive"))
    )
    (net (code "45") (name "12V") (class "Default")
      (node (ref "C66") (pin "1") (pinfunction "1_1") (pintype "passive"))
      (node (ref "C70") (pin "2") (pinfunction "2_2") (pintype "passive"))
      (node (ref "C78") (pin "1") (pinfunction "1_1") (pintype "passive"))
      (node (ref "C80") (pin "2") (pinfunction "2_2") (pintype "passive"))
      (node (ref "U18") (pin "5") (pinfunction "~{SHDN}_5") (pintype "input"))
      (node (ref "U18") (pin "8") (pinfunction "IN_8") (pintype "power_in"))
      (node (ref "U23") (pin "2") (pinfunction "VIN_2") (pintype "power_in"))
    )
    (net (code "46") (name "24V") (class "Default")
      (node (ref "C74") (pin "1") (pinfunction "1_1") (pintype "passive"))
      (node (ref "U20") (pin "5") (pinfunction "VBB_5") (pintype "power_in"))
      (node (ref "U20") (pin "6") (pinfunction "VBB_6") (pintype "power_in"))
      (node (ref "U20") (pin "7") (pinfunction "VBB_7") (pintype "power_in"))
      (node (ref "U20") (pin "8") (pinfunction "VBB_8") (pintype "power_in"))
    )
    (net (code "47") (name "GND") (class "Default")
      (node (ref "C27") (pin "2") (pinfunction "2_2") (pintype "passive"))
      (node (ref "C66") (pin "2") (pinfunction "2_2") (pintype "passive"))
      (node (ref "C68") (pin "2") (pinfunction "2_2") (pintype "passive"))
      (node (ref "C69") (pin "2") (pinfunction "2_2") (pintype "passive"))
      (node (ref "C70") (pin "1") (pinfunction "1_1") (pintype "passive"))
      (node (ref "C71") (pin "1") (pinfunction "1_1") (pintype "passive"))
      (node (ref "C72") (pin "2") (pinfunction "2_2") (pintype "passive"))
      (node (ref "C73") (pin "2") (pinfunction "2_2") (pintype "passive"))
      (node (ref "C74") (pin "2") (pinfunction "2_2") (pintype "passive"))
      (node (ref "C75") (pin "2") (pinfunction "2_2") (pintype "passive"))
      (node (ref "C76") (pin "2") (pinfunction "2_2") (pintype "passive"))
      (node (ref "C77") (pin "1") (pinfunction "1_1") (pintype "passive"))
      (node (ref "C78") (pin "2") (pinfunction "2_2") (pintype "passive"))
      (node (ref "C79") (pin "2") (pinfunction "2_2") (pintype "passive"))
      (node (ref "C80") (pin "1") (pinfunction "1_1") (pintype "passive"))
      (node (ref "C81") (pin "1") (pinfunction "1_1") (pintype "passive"))
      (node (ref "C82") (pin "2") (pinfunction "2_2") (pintype "passive"))
      (node (ref "C83") (pin "1") (pinfunction "1_1") (pintype "passive"))
      (node (ref "C84") (pin "2") (pinfunction "2_2") (pintype "passive"))
      (node (ref "C85") (pin "1") (pinfunction "1_1") (pintype "passive"))
      (node (ref "C86") (pin "1") (pinfunction "1_1") (pintype "passive"))
      (node (ref "C88") (pin "1") (pinfunction "1_1") (pintype "passive"))
      (node (ref "D17") (pin "2") (pinfunction "A_2") (pintype "passive"))
      (node (ref "D18") (pin "2") (pinfunction "A_2") (pintype "passive"))
      (node (ref "D19") (pin "2") (pinfunction "A_2") (pintype "passive"))
      (node (ref "D20") (pin "2") (pinfunction "A_2") (pintype "passive"))
      (node (ref "D21") (pin "2") (pinfunction "A_2") (pintype "passive"))
      (node (ref "D22") (pin "2") (pinfunction "A_2") (pintype "passive"))
      (node (ref "R64") (pin "1") (pinfunction "1_1") (pintype "passive"))
      (node (ref "R65") (pin "1") (pinfunction "1_1") (pintype "passive"))
      (node (ref "R67") (pin "2") (pinfunction "2_2") (pintype "passive"))
      (node (ref "R71") (pin "1") (pinfunction "1_1") (pintype "passive"))
      (node (ref "R74") (pin "1") (pinfunction "1_1") (pintype "passive"))
      (node (ref "R75") (pin "1") (pinfunction "1_1") (pintype "passive"))
      (node (ref "R80") (pin "1") (pinfunction "1_1") (pintype "passive"))
      (node (ref "R81") (pin "1") (pinfunction "1_1") (pintype "passive"))
      (node (ref "U18") (pin "3") (pinfunction "GND_3") (pintype "power_in"))
      (node (ref "U18") (pin "6") (pinfunction "GND_6") (pintype "power_in"))
      (node (ref "U18") (pin "7") (pinfunction "GND_7") (pintype "power_in"))
      (node (ref "U19") (pin "4") (pinfunction "V-_4") (pintype "power_in"))
      (node (ref "U20") (pin "1") (pinfunction "GND_1") (pintype "power_in"))
      (node (ref "U22") (pin "4") (pinfunction "V-_4") (pintype "power_in"))
      (node (ref "U23") (pin "4") (pinfunction "GND_4") (pintype "power_in"))
      (node (ref "U24") (pin "4") (pinfunction "V-_4") (pintype "power_in"))
      (node (ref "U25") (pin "1") (pinfunction "1~{OE}_1") (pintype "passive"))
      (node (ref "U25") (pin "10") (pinfunction "3~{OE}_10") (pintype "passive"))
      (node (ref "U25") (pin "12") (pinfunction "4A_12") (pintype "passive"))
      (node (ref "U25") (pin "4") (pinfunction "2~{OE}_4") (pintype "passive"))
      (node (ref "U25") (pin "7") (pinfunction "GND_7") (pintype "passive"))
      (node (ref "U26") (pin "1") (pinfunction "~{LAT1}_1") (pintype "passive"))
      (node (ref "U26") (pin "20") (pinfunction "~{LAT0}/HVC_20") (pintype "passive"))
      (node (ref "U26") (pin "9") (pinfunction "VSS_9") (pintype "passive"))
    )
    (net (code "48") (name "Net-(U23A-TRIM{slash}NR)") (class "Default")
      (node (ref "C27") (pin "1") (pinfunction "1_1") (pintype "passive"))
      (node (ref "U23") (pin "5") (pinfunction "TRIM/NR_5") (pintype "input"))
    )
    (net (code "49") (name "unconnected-(U20-NC-Pad4)") (class "Default")
      (node (ref "U20") (pin "4") (pinfunction "NC_4") (pintype "passive+no_connect"))
    )
    (net (code "50") (name "unconnected-(U23A-TEMP-Pad3)") (class "Default")
      (node (ref "U23") (pin "3") (pinfunction "TEMP_3") (pintype "output+no_connect"))
    )
    (net (code "51") (name "unconnected-(U23B-DNC-Pad1)") (class "Default")
      (node (ref "U23") (pin "1") (pinfunction "DNC_1") (pintype "passive+no_connect"))
    )
    (net (code "52") (name "unconnected-(U23B-DNC-Pad8)") (class "Default")
      (node (ref "U23") (pin "8") (pinfunction "DNC_8") (pintype "passive+no_connect"))
    )
    (net (code "53") (name "unconnected-(U23B-NC-Pad7)") (class "Default")
      (node (ref "U23") (pin "7") (pinfunction "NC_7") (pintype "passive+no_connect"))
    )
    (net (code "54") (name "unconnected-(U25-4Y-Pad11)") (class "Default")
      (node (ref "U25") (pin "11") (pinfunction "4Y_11") (pintype "passive+no_connect"))
    )
    (net (code "55") (name "unconnected-(U26-NC_1-Pad10)") (class "Default")
      (node (ref "U26") (pin "10") (pinfunction "NC_1_10") (pintype "passive+no_connect"))
    )
    (net (code "56") (name "unconnected-(U26-NC_2-Pad11)") (class "Default")
      (node (ref "U26") (pin "11") (pinfunction "NC_2_11") (pintype "passive+no_connect"))
    )
    (net (code "57") (name "unconnected-(U26-SDO-Pad17)") (class "Default")
      (node (ref "U26") (pin "17") (pinfunction "SDO_17") (pintype "passive+no_connect"))
    )
    (net (code "58") (name "unconnected-(U26-VOUT6-Pad8)") (class "Default")
      (node (ref "U26") (pin "8") (pinfunction "VOUT6_8") (pintype "passive+no_connect"))
    )
    (net (code "59") (name "unconnected-(U26-VOUT7-Pad12)") (class "Default")
      (node (ref "U26") (pin "12") (pinfunction "VOUT7_12") (pintype "passive+no_connect"))
    )
  )
)
